# Schematic.net
KiCad netlist of a schematic drawn in EAGLE
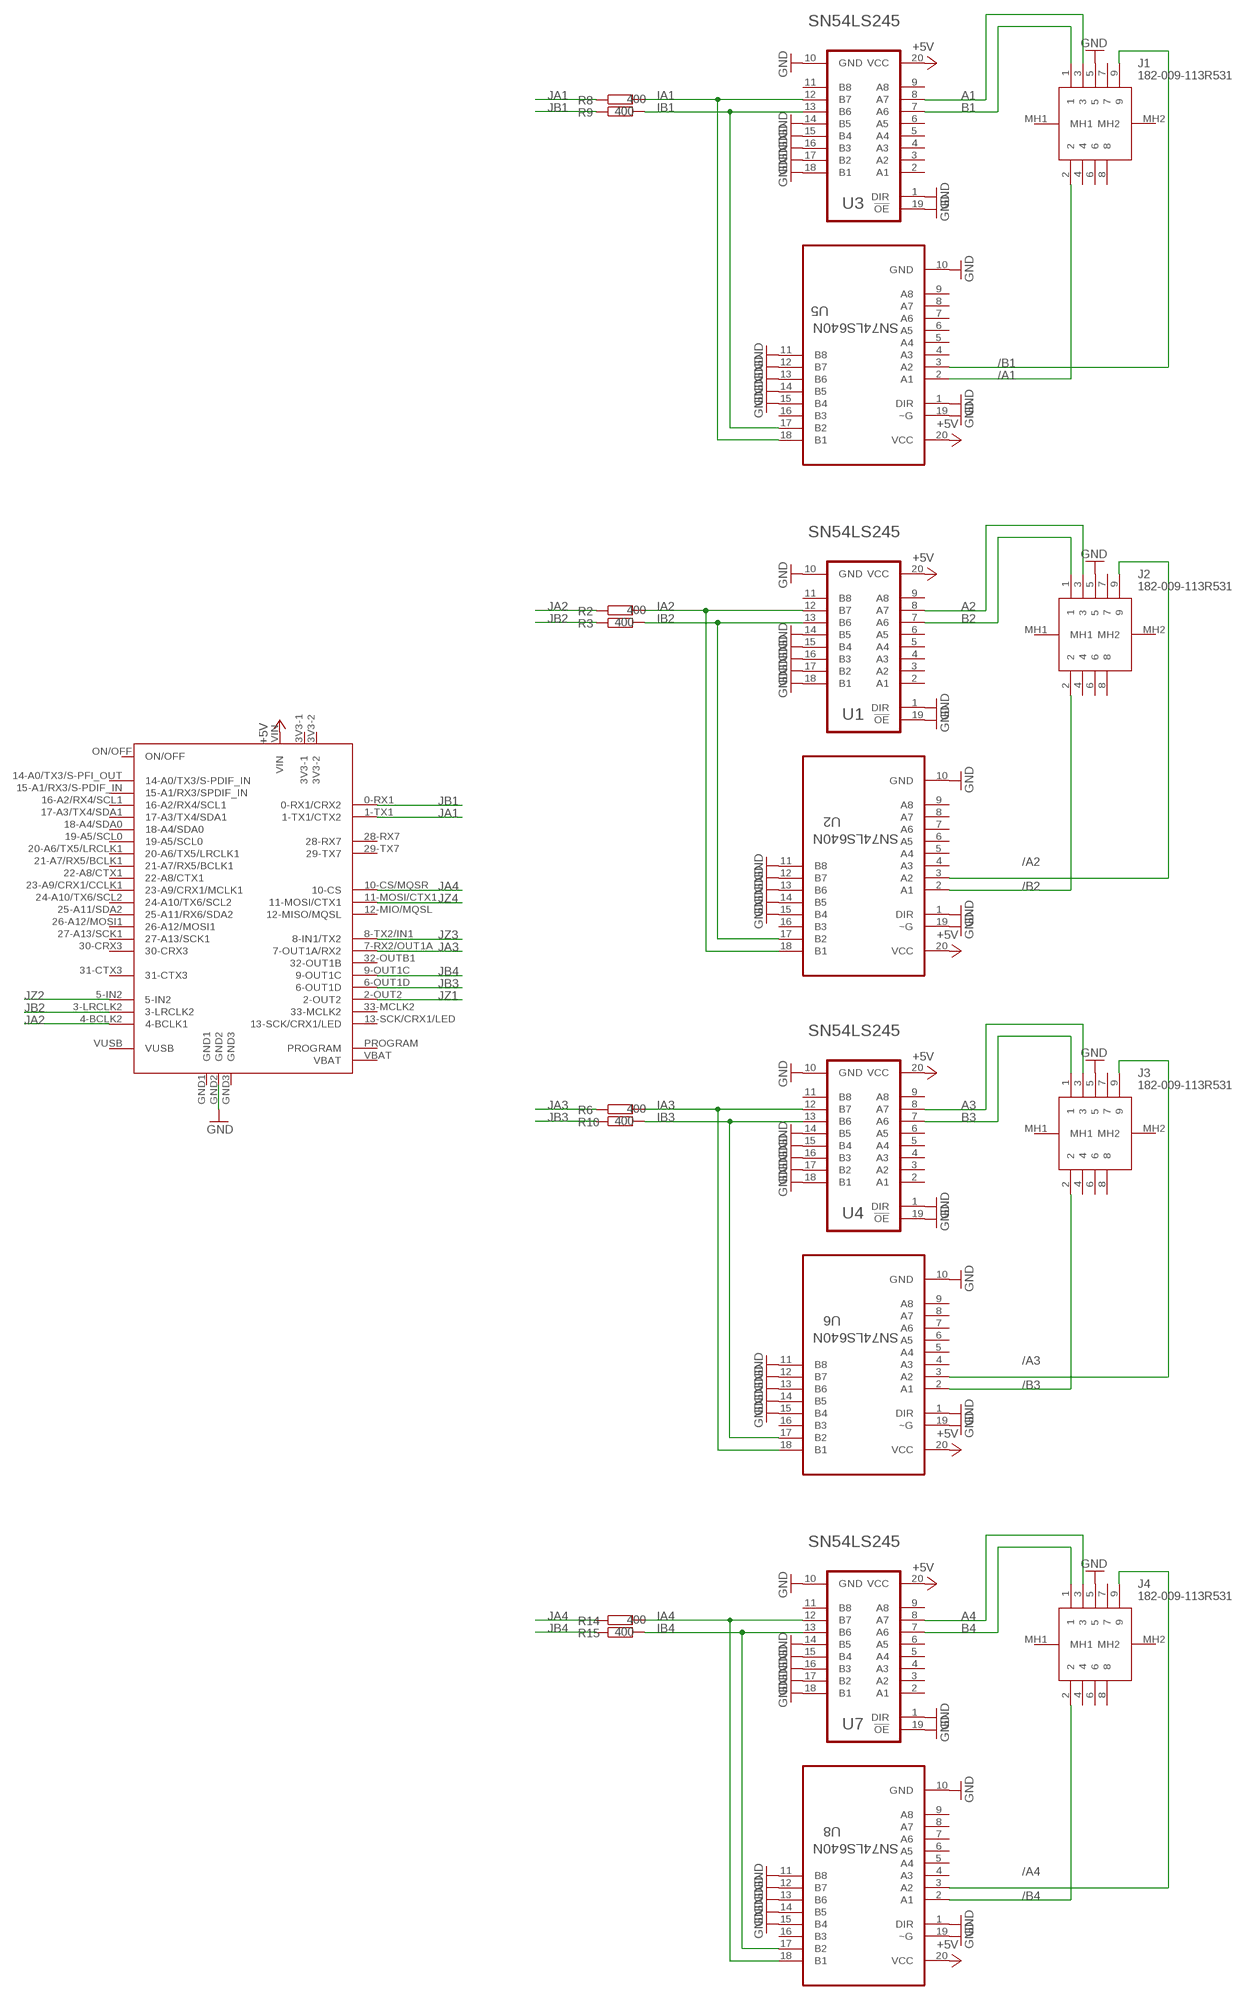
[diagram p0: schematic, sheet 1]

(export (version "E")
  (design (tool "Eeschema 10.0.6"))
  (components
    (comp (ref "J1")
      (value "182-009-113R531")
      (footprint "eagle-import:182009113R531")
      (fields (field (name "MOUSER_PART_NUMBER") "636-182-009-113R531"))
      (libsource (lib "eagle-import") (part "182-009-113R531"))
    )
    (comp (ref "J2")
      (value "182-009-113R531")
      (footprint "eagle-import:182009113R531")
      (fields (field (name "MOUSER_PART_NUMBER") "636-182-009-113R531"))
      (libsource (lib "eagle-import") (part "182-009-113R531"))
    )
    (comp (ref "J3")
      (value "182-009-113R531")
      (footprint "eagle-import:182009113R531")
      (fields (field (name "MOUSER_PART_NUMBER") "636-182-009-113R531"))
      (libsource (lib "eagle-import") (part "182-009-113R531"))
    )
    (comp (ref "J4")
      (value "182-009-113R531")
      (footprint "eagle-import:182009113R531")
      (fields (field (name "MOUSER_PART_NUMBER") "636-182-009-113R531"))
      (libsource (lib "eagle-import") (part "182-009-113R531"))
    )
    (comp (ref "R2")
      (value "400")
      (footprint "eagle-import:0204_7")
      (libsource (lib "eagle-import") (part "R-EU_0204/7"))
    )
    (comp (ref "R3")
      (value "400")
      (footprint "eagle-import:0204_7")
      (libsource (lib "eagle-import") (part "R-EU_0204/7"))
    )
    (comp (ref "R6")
      (value "400")
      (footprint "eagle-import:0204_7")
      (libsource (lib "eagle-import") (part "R-EU_0204/7"))
    )
    (comp (ref "R8")
      (value "400")
      (footprint "eagle-import:0204_7")
      (libsource (lib "eagle-import") (part "R-EU_0204/7"))
    )
    (comp (ref "R9")
      (value "400")
      (footprint "eagle-import:0204_7")
      (libsource (lib "eagle-import") (part "R-EU_0204/7"))
    )
    (comp (ref "R10")
      (value "400")
      (footprint "eagle-import:0204_7")
      (libsource (lib "eagle-import") (part "R-EU_0204/7"))
    )
    (comp (ref "R14")
      (value "400")
      (footprint "eagle-import:0204_7")
      (libsource (lib "eagle-import") (part "R-EU_0204/7"))
    )
    (comp (ref "R15")
      (value "400")
      (footprint "eagle-import:0204_7")
      (libsource (lib "eagle-import") (part "R-EU_0204/7"))
    )
    (comp (ref "U$1")
      (value "TEENSY40")
      (footprint "eagle-import:TEENSY40")
      (libsource (lib "eagle-import") (part "TEENSY40"))
    )
    (comp (ref "U1")
      (value "TEXAS_INSTRUMENTS_SN54LS245TEXAS_INSTRUMENTS_SN54LS245_0_0")
      (footprint "eagle-import:TEXAS_INSTRUMENTS_SN54LS245_0")
      (fields (field (name "MF") "Texas Instruments") (field (name "MPN") "SN54LS245"))
      (libsource (lib "eagle-import") (part "TEXAS_INSTRUMENTS_SN54LS245TEXAS_INSTRUMENTS_SN54LS245_0_0"))
    )
    (comp (ref "U2")
      (value "SN74LS640N")
      (footprint "eagle-import:DIP254P762X508-20")
      (fields (field (name "MF") "Texas Instruments"))
      (libsource (lib "eagle-import") (part "SN74LS640N"))
    )
    (comp (ref "U3")
      (value "TEXAS_INSTRUMENTS_SN54LS245TEXAS_INSTRUMENTS_SN54LS245_0_0")
      (footprint "eagle-import:TEXAS_INSTRUMENTS_SN54LS245_0")
      (fields (field (name "MF") "Texas Instruments") (field (name "MPN") "SN54LS245"))
      (libsource (lib "eagle-import") (part "TEXAS_INSTRUMENTS_SN54LS245TEXAS_INSTRUMENTS_SN54LS245_0_0"))
    )
    (comp (ref "U4")
      (value "TEXAS_INSTRUMENTS_SN54LS245TEXAS_INSTRUMENTS_SN54LS245_0_0")
      (footprint "eagle-import:TEXAS_INSTRUMENTS_SN54LS245_0")
      (fields (field (name "MF") "Texas Instruments") (field (name "MPN") "SN54LS245"))
      (libsource (lib "eagle-import") (part "TEXAS_INSTRUMENTS_SN54LS245TEXAS_INSTRUMENTS_SN54LS245_0_0"))
    )
    (comp (ref "U5")
      (value "SN74LS640N")
      (footprint "eagle-import:DIP254P762X508-20")
      (fields (field (name "MF") "Texas Instruments"))
      (libsource (lib "eagle-import") (part "SN74LS640N"))
    )
    (comp (ref "U6")
      (value "SN74LS640N")
      (footprint "eagle-import:DIP254P762X508-20")
      (fields (field (name "MF") "Texas Instruments"))
      (libsource (lib "eagle-import") (part "SN74LS640N"))
    )
    (comp (ref "U7")
      (value "TEXAS_INSTRUMENTS_SN54LS245TEXAS_INSTRUMENTS_SN54LS245_0_0")
      (footprint "eagle-import:TEXAS_INSTRUMENTS_SN54LS245_0")
      (fields (field (name "MF") "Texas Instruments") (field (name "MPN") "SN54LS245"))
      (libsource (lib "eagle-import") (part "TEXAS_INSTRUMENTS_SN54LS245TEXAS_INSTRUMENTS_SN54LS245_0_0"))
    )
    (comp (ref "U8")
      (value "SN74LS640N")
      (footprint "eagle-import:DIP254P762X508-20")
      (fields (field (name "MF") "Texas Instruments"))
      (libsource (lib "eagle-import") (part "SN74LS640N"))
    )
  )
  (nets
    (net (code "1") (name "+5V") (class "Default")
      (node (ref "U$1") (pin "VIN") (pinfunction "VIN_VIN") (pintype "bidirectional"))
      (node (ref "U1") (pin "20") (pinfunction "VCC_20") (pintype "power_in"))
      (node (ref "U2") (pin "20") (pinfunction "VCC_20") (pintype "power_in"))
      (node (ref "U3") (pin "20") (pinfunction "VCC_20") (pintype "power_in"))
      (node (ref "U4") (pin "20") (pinfunction "VCC_20") (pintype "power_in"))
      (node (ref "U5") (pin "20") (pinfunction "VCC_20") (pintype "power_in"))
      (node (ref "U6") (pin "20") (pinfunction "VCC_20") (pintype "power_in"))
      (node (ref "U7") (pin "20") (pinfunction "VCC_20") (pintype "power_in"))
      (node (ref "U8") (pin "20") (pinfunction "VCC_20") (pintype "power_in"))
    )
    (net (code "2") (name "/A1") (class "Default")
      (node (ref "J1") (pin "3") (pinfunction "3_3") (pintype "bidirectional"))
      (node (ref "U3") (pin "8") (pinfunction "A7_8") (pintype "bidirectional"))
    )
    (net (code "3") (name "/A2") (class "Default")
      (node (ref "J2") (pin "3") (pinfunction "3_3") (pintype "bidirectional"))
      (node (ref "U1") (pin "8") (pinfunction "A7_8") (pintype "bidirectional"))
    )
    (net (code "4") (name "/A3") (class "Default")
      (node (ref "J3") (pin "3") (pinfunction "3_3") (pintype "bidirectional"))
      (node (ref "U4") (pin "8") (pinfunction "A7_8") (pintype "bidirectional"))
    )
    (net (code "5") (name "/A4") (class "Default")
      (node (ref "J4") (pin "3") (pinfunction "3_3") (pintype "bidirectional"))
      (node (ref "U7") (pin "8") (pinfunction "A7_8") (pintype "bidirectional"))
    )
    (net (code "6") (name "/B1") (class "Default")
      (node (ref "J1") (pin "1") (pinfunction "1_1") (pintype "bidirectional"))
      (node (ref "U3") (pin "7") (pinfunction "A6_7") (pintype "bidirectional"))
    )
    (net (code "7") (name "/B2") (class "Default")
      (node (ref "J2") (pin "1") (pinfunction "1_1") (pintype "bidirectional"))
      (node (ref "U1") (pin "7") (pinfunction "A6_7") (pintype "bidirectional"))
    )
    (net (code "8") (name "/B3") (class "Default")
      (node (ref "J3") (pin "1") (pinfunction "1_1") (pintype "bidirectional"))
      (node (ref "U4") (pin "7") (pinfunction "A6_7") (pintype "bidirectional"))
    )
    (net (code "9") (name "/B4") (class "Default")
      (node (ref "J4") (pin "1") (pinfunction "1_1") (pintype "bidirectional"))
      (node (ref "U7") (pin "7") (pinfunction "A6_7") (pintype "bidirectional"))
    )
    (net (code "10") (name "/IA1") (class "Default")
      (node (ref "R8") (pin "2") (pinfunction "2_2") (pintype "passive"))
      (node (ref "U3") (pin "12") (pinfunction "B7_12") (pintype "bidirectional"))
      (node (ref "U5") (pin "18") (pinfunction "B1_18") (pintype "bidirectional"))
    )
    (net (code "11") (name "/IA2") (class "Default")
      (node (ref "R2") (pin "2") (pinfunction "2_2") (pintype "passive"))
      (node (ref "U1") (pin "12") (pinfunction "B7_12") (pintype "bidirectional"))
      (node (ref "U2") (pin "18") (pinfunction "B1_18") (pintype "bidirectional"))
    )
    (net (code "12") (name "/IA3") (class "Default")
      (node (ref "R6") (pin "2") (pinfunction "2_2") (pintype "passive"))
      (node (ref "U4") (pin "12") (pinfunction "B7_12") (pintype "bidirectional"))
      (node (ref "U6") (pin "18") (pinfunction "B1_18") (pintype "bidirectional"))
    )
    (net (code "13") (name "/IA4") (class "Default")
      (node (ref "R14") (pin "2") (pinfunction "2_2") (pintype "passive"))
      (node (ref "U7") (pin "12") (pinfunction "B7_12") (pintype "bidirectional"))
      (node (ref "U8") (pin "18") (pinfunction "B1_18") (pintype "bidirectional"))
    )
    (net (code "14") (name "/IB1") (class "Default")
      (node (ref "R9") (pin "2") (pinfunction "2_2") (pintype "passive"))
      (node (ref "U3") (pin "13") (pinfunction "B6_13") (pintype "bidirectional"))
      (node (ref "U5") (pin "17") (pinfunction "B2_17") (pintype "bidirectional"))
    )
    (net (code "15") (name "/IB2") (class "Default")
      (node (ref "R3") (pin "2") (pinfunction "2_2") (pintype "passive"))
      (node (ref "U1") (pin "13") (pinfunction "B6_13") (pintype "bidirectional"))
      (node (ref "U2") (pin "17") (pinfunction "B2_17") (pintype "bidirectional"))
    )
    (net (code "16") (name "/IB3") (class "Default")
      (node (ref "R10") (pin "2") (pinfunction "2_2") (pintype "passive"))
      (node (ref "U4") (pin "13") (pinfunction "B6_13") (pintype "bidirectional"))
      (node (ref "U6") (pin "17") (pinfunction "B2_17") (pintype "bidirectional"))
    )
    (net (code "17") (name "/IB4") (class "Default")
      (node (ref "R15") (pin "2") (pinfunction "2_2") (pintype "passive"))
      (node (ref "U7") (pin "13") (pinfunction "B6_13") (pintype "bidirectional"))
      (node (ref "U8") (pin "17") (pinfunction "B2_17") (pintype "bidirectional"))
    )
    (net (code "18") (name "/JA1") (class "Default")
      (node (ref "R8") (pin "1") (pinfunction "1_1") (pintype "passive"))
      (node (ref "U$1") (pin "1-TX1") (pinfunction "1-TX1/CTX2_1-TX1") (pintype "bidirectional"))
    )
    (net (code "19") (name "/JA2") (class "Default")
      (node (ref "R2") (pin "1") (pinfunction "1_1") (pintype "passive"))
      (node (ref "U$1") (pin "4-BCLK2") (pinfunction "4-BCLK1_4-BCLK2") (pintype "bidirectional"))
    )
    (net (code "20") (name "/JA3") (class "Default")
      (node (ref "R6") (pin "1") (pinfunction "1_1") (pintype "passive"))
      (node (ref "U$1") (pin "7-RX2/OUT1A") (pinfunction "7-OUT1A/RX2_7-RX2/OUT1A") (pintype "bidirectional"))
    )
    (net (code "21") (name "/JA4") (class "Default")
      (node (ref "R14") (pin "1") (pinfunction "1_1") (pintype "passive"))
      (node (ref "U$1") (pin "10-CS/MQSR") (pinfunction "10-CS_10-CS/MQSR") (pintype "bidirectional"))
    )
    (net (code "22") (name "/JB1") (class "Default")
      (node (ref "R9") (pin "1") (pinfunction "1_1") (pintype "passive"))
      (node (ref "U$1") (pin "0-RX1") (pinfunction "0-RX1/CRX2_0-RX1") (pintype "bidirectional"))
    )
    (net (code "23") (name "/JB2") (class "Default")
      (node (ref "R3") (pin "1") (pinfunction "1_1") (pintype "passive"))
      (node (ref "U$1") (pin "3-LRCLK2") (pinfunction "3-LRCLK2_3-LRCLK2") (pintype "bidirectional"))
    )
    (net (code "24") (name "/JB3") (class "Default")
      (node (ref "R10") (pin "1") (pinfunction "1_1") (pintype "passive"))
      (node (ref "U$1") (pin "6-OUT1D") (pinfunction "6-OUT1D_6-OUT1D") (pintype "bidirectional"))
    )
    (net (code "25") (name "/JB4") (class "Default")
      (node (ref "R15") (pin "1") (pinfunction "1_1") (pintype "passive"))
      (node (ref "U$1") (pin "9-OUT1C") (pinfunction "9-OUT1C_9-OUT1C") (pintype "bidirectional"))
    )
    (net (code "26") (name "/JZ1") (class "Default")
      (node (ref "U$1") (pin "2-OUT2") (pinfunction "2-OUT2_2-OUT2") (pintype "bidirectional"))
    )
    (net (code "27") (name "/JZ2") (class "Default")
      (node (ref "U$1") (pin "5-IN2") (pinfunction "5-IN2_5-IN2") (pintype "bidirectional"))
    )
    (net (code "28") (name "/JZ3") (class "Default")
      (node (ref "U$1") (pin "8-TX2/IN1") (pinfunction "8-IN1/TX2_8-TX2/IN1") (pintype "bidirectional"))
    )
    (net (code "29") (name "/JZ4") (class "Default")
      (node (ref "U$1") (pin "11-MOSI/CTX1") (pinfunction "11-MOSI/CTX1_11-MOSI/CTX1") (pintype "bidirectional"))
    )
    (net (code "30") (name "/{slash}A1") (class "Default")
      (node (ref "J1") (pin "2") (pinfunction "2_2") (pintype "bidirectional"))
      (node (ref "U5") (pin "2") (pinfunction "A1_2") (pintype "bidirectional"))
    )
    (net (code "31") (name "/{slash}A2") (class "Default")
      (node (ref "J2") (pin "2") (pinfunction "2_2") (pintype "bidirectional"))
      (node (ref "U2") (pin "2") (pinfunction "A1_2") (pintype "bidirectional"))
    )
    (net (code "32") (name "/{slash}A3") (class "Default")
      (node (ref "J3") (pin "2") (pinfunction "2_2") (pintype "bidirectional"))
      (node (ref "U6") (pin "2") (pinfunction "A1_2") (pintype "bidirectional"))
    )
    (net (code "33") (name "/{slash}A4") (class "Default")
      (node (ref "J4") (pin "2") (pinfunction "2_2") (pintype "bidirectional"))
      (node (ref "U8") (pin "2") (pinfunction "A1_2") (pintype "bidirectional"))
    )
    (net (code "34") (name "/{slash}B1") (class "Default")
      (node (ref "J1") (pin "9") (pinfunction "9_9") (pintype "bidirectional"))
      (node (ref "U5") (pin "3") (pinfunction "A2_3") (pintype "bidirectional"))
    )
    (net (code "35") (name "/{slash}B2") (class "Default")
      (node (ref "J2") (pin "9") (pinfunction "9_9") (pintype "bidirectional"))
      (node (ref "U2") (pin "3") (pinfunction "A2_3") (pintype "bidirectional"))
    )
    (net (code "36") (name "/{slash}B3") (class "Default")
      (node (ref "J3") (pin "9") (pinfunction "9_9") (pintype "bidirectional"))
      (node (ref "U6") (pin "3") (pinfunction "A2_3") (pintype "bidirectional"))
    )
    (net (code "37") (name "/{slash}B4") (class "Default")
      (node (ref "J4") (pin "9") (pinfunction "9_9") (pintype "bidirectional"))
      (node (ref "U8") (pin "3") (pinfunction "A2_3") (pintype "bidirectional"))
    )
    (net (code "38") (name "GND") (class "Default")
      (node (ref "J1") (pin "5") (pinfunction "5_5") (pintype "bidirectional"))
      (node (ref "J2") (pin "5") (pinfunction "5_5") (pintype "bidirectional"))
      (node (ref "J3") (pin "5") (pinfunction "5_5") (pintype "bidirectional"))
      (node (ref "J4") (pin "5") (pinfunction "5_5") (pintype "bidirectional"))
      (node (ref "U$1") (pin "GND2") (pinfunction "GND2_GND2") (pintype "bidirectional"))
      (node (ref "U1") (pin "1") (pinfunction "DIR_1") (pintype "input"))
      (node (ref "U1") (pin "10") (pinfunction "GND_10") (pintype "power_in"))
      (node (ref "U1") (pin "14") (pinfunction "B5_14") (pintype "bidirectional"))
      (node (ref "U1") (pin "15") (pinfunction "B4_15") (pintype "bidirectional"))
      (node (ref "U1") (pin "16") (pinfunction "B3_16") (pintype "bidirectional"))
      (node (ref "U1") (pin "17") (pinfunction "B2_17") (pintype "bidirectional"))
      (node (ref "U1") (pin "18") (pinfunction "B1_18") (pintype "bidirectional"))
      (node (ref "U1") (pin "19") (pinfunction "~{OE}_19") (pintype "input"))
      (node (ref "U2") (pin "1") (pinfunction "DIR_1") (pintype "input"))
      (node (ref "U2") (pin "10") (pinfunction "GND_10") (pintype "passive"))
      (node (ref "U2") (pin "11") (pinfunction "B8_11") (pintype "bidirectional"))
      (node (ref "U2") (pin "12") (pinfunction "B7_12") (pintype "bidirectional"))
      (node (ref "U2") (pin "13") (pinfunction "B6_13") (pintype "bidirectional"))
      (node (ref "U2") (pin "14") (pinfunction "B5_14") (pintype "bidirectional"))
      (node (ref "U2") (pin "15") (pinfunction "B4_15") (pintype "bidirectional"))
      (node (ref "U2") (pin "19") (pinfunction "~{G}_19") (pintype "input"))
      (node (ref "U3") (pin "1") (pinfunction "DIR_1") (pintype "input"))
      (node (ref "U3") (pin "10") (pinfunction "GND_10") (pintype "power_in"))
      (node (ref "U3") (pin "14") (pinfunction "B5_14") (pintype "bidirectional"))
      (node (ref "U3") (pin "15") (pinfunction "B4_15") (pintype "bidirectional"))
      (node (ref "U3") (pin "16") (pinfunction "B3_16") (pintype "bidirectional"))
      (node (ref "U3") (pin "17") (pinfunction "B2_17") (pintype "bidirectional"))
      (node (ref "U3") (pin "18") (pinfunction "B1_18") (pintype "bidirectional"))
      (node (ref "U3") (pin "19") (pinfunction "~{OE}_19") (pintype "input"))
      (node (ref "U4") (pin "1") (pinfunction "DIR_1") (pintype "input"))
      (node (ref "U4") (pin "10") (pinfunction "GND_10") (pintype "power_in"))
      (node (ref "U4") (pin "14") (pinfunction "B5_14") (pintype "bidirectional"))
      (node (ref "U4") (pin "15") (pinfunction "B4_15") (pintype "bidirectional"))
      (node (ref "U4") (pin "16") (pinfunction "B3_16") (pintype "bidirectional"))
      (node (ref "U4") (pin "17") (pinfunction "B2_17") (pintype "bidirectional"))
      (node (ref "U4") (pin "18") (pinfunction "B1_18") (pintype "bidirectional"))
      (node (ref "U4") (pin "19") (pinfunction "~{OE}_19") (pintype "input"))
      (node (ref "U5") (pin "1") (pinfunction "DIR_1") (pintype "input"))
      (node (ref "U5") (pin "10") (pinfunction "GND_10") (pintype "passive"))
      (node (ref "U5") (pin "11") (pinfunction "B8_11") (pintype "bidirectional"))
      (node (ref "U5") (pin "12") (pinfunction "B7_12") (pintype "bidirectional"))
      (node (ref "U5") (pin "13") (pinfunction "B6_13") (pintype "bidirectional"))
      (node (ref "U5") (pin "14") (pinfunction "B5_14") (pintype "bidirectional"))
      (node (ref "U5") (pin "15") (pinfunction "B4_15") (pintype "bidirectional"))
      (node (ref "U5") (pin "19") (pinfunction "~{G}_19") (pintype "input"))
      (node (ref "U6") (pin "1") (pinfunction "DIR_1") (pintype "input"))
      (node (ref "U6") (pin "10") (pinfunction "GND_10") (pintype "passive"))
      (node (ref "U6") (pin "11") (pinfunction "B8_11") (pintype "bidirectional"))
      (node (ref "U6") (pin "12") (pinfunction "B7_12") (pintype "bidirectional"))
      (node (ref "U6") (pin "13") (pinfunction "B6_13") (pintype "bidirectional"))
      (node (ref "U6") (pin "14") (pinfunction "B5_14") (pintype "bidirectional"))
      (node (ref "U6") (pin "15") (pinfunction "B4_15") (pintype "bidirectional"))
      (node (ref "U6") (pin "19") (pinfunction "~{G}_19") (pintype "input"))
      (node (ref "U7") (pin "1") (pinfunction "DIR_1") (pintype "input"))
      (node (ref "U7") (pin "10") (pinfunction "GND_10") (pintype "power_in"))
      (node (ref "U7") (pin "14") (pinfunction "B5_14") (pintype "bidirectional"))
      (node (ref "U7") (pin "15") (pinfunction "B4_15") (pintype "bidirectional"))
      (node (ref "U7") (pin "16") (pinfunction "B3_16") (pintype "bidirectional"))
      (node (ref "U7") (pin "17") (pinfunction "B2_17") (pintype "bidirectional"))
      (node (ref "U7") (pin "18") (pinfunction "B1_18") (pintype "bidirectional"))
      (node (ref "U7") (pin "19") (pinfunction "~{OE}_19") (pintype "input"))
      (node (ref "U8") (pin "1") (pinfunction "DIR_1") (pintype "input"))
      (node (ref "U8") (pin "10") (pinfunction "GND_10") (pintype "passive"))
      (node (ref "U8") (pin "11") (pinfunction "B8_11") (pintype "bidirectional"))
      (node (ref "U8") (pin "12") (pinfunction "B7_12") (pintype "bidirectional"))
      (node (ref "U8") (pin "13") (pinfunction "B6_13") (pintype "bidirectional"))
      (node (ref "U8") (pin "14") (pinfunction "B5_14") (pintype "bidirectional"))
      (node (ref "U8") (pin "15") (pinfunction "B4_15") (pintype "bidirectional"))
      (node (ref "U8") (pin "19") (pinfunction "~{G}_19") (pintype "input"))
    )
    (net (code "39") (name "unconnected-(J1-Pad4)") (class "Default")
      (node (ref "J1") (pin "4") (pinfunction "4_4") (pintype "bidirectional"))
    )
    (net (code "40") (name "unconnected-(J1-Pad6)") (class "Default")
      (node (ref "J1") (pin "6") (pinfunction "6_6") (pintype "bidirectional"))
    )
    (net (code "41") (name "unconnected-(J1-Pad7)") (class "Default")
      (node (ref "J1") (pin "7") (pinfunction "7_7") (pintype "bidirectional"))
    )
    (net (code "42") (name "unconnected-(J1-Pad8)") (class "Default")
      (node (ref "J1") (pin "8") (pinfunction "8_8") (pintype "bidirectional"))
    )
    (net (code "43") (name "unconnected-(J1-PadMH1)") (class "Default")
      (node (ref "J1") (pin "MH1") (pinfunction "MH1_MH1") (pintype "bidirectional"))
    )
    (net (code "44") (name "unconnected-(J1-PadMH2)") (class "Default")
      (node (ref "J1") (pin "MH2") (pinfunction "MH2_MH2") (pintype "bidirectional"))
    )
    (net (code "45") (name "unconnected-(J2-Pad4)") (class "Default")
      (node (ref "J2") (pin "4") (pinfunction "4_4") (pintype "bidirectional"))
    )
    (net (code "46") (name "unconnected-(J2-Pad6)") (class "Default")
      (node (ref "J2") (pin "6") (pinfunction "6_6") (pintype "bidirectional"))
    )
    (net (code "47") (name "unconnected-(J2-Pad7)") (class "Default")
      (node (ref "J2") (pin "7") (pinfunction "7_7") (pintype "bidirectional"))
    )
    (net (code "48") (name "unconnected-(J2-Pad8)") (class "Default")
      (node (ref "J2") (pin "8") (pinfunction "8_8") (pintype "bidirectional"))
    )
    (net (code "49") (name "unconnected-(J2-PadMH1)") (class "Default")
      (node (ref "J2") (pin "MH1") (pinfunction "MH1_MH1") (pintype "bidirectional"))
    )
    (net (code "50") (name "unconnected-(J2-PadMH2)") (class "Default")
      (node (ref "J2") (pin "MH2") (pinfunction "MH2_MH2") (pintype "bidirectional"))
    )
    (net (code "51") (name "unconnected-(J3-Pad4)") (class "Default")
      (node (ref "J3") (pin "4") (pinfunction "4_4") (pintype "bidirectional"))
    )
    (net (code "52") (name "unconnected-(J3-Pad6)") (class "Default")
      (node (ref "J3") (pin "6") (pinfunction "6_6") (pintype "bidirectional"))
    )
    (net (code "53") (name "unconnected-(J3-Pad7)") (class "Default")
      (node (ref "J3") (pin "7") (pinfunction "7_7") (pintype "bidirectional"))
    )
    (net (code "54") (name "unconnected-(J3-Pad8)") (class "Default")
      (node (ref "J3") (pin "8") (pinfunction "8_8") (pintype "bidirectional"))
    )
    (net (code "55") (name "unconnected-(J3-PadMH1)") (class "Default")
      (node (ref "J3") (pin "MH1") (pinfunction "MH1_MH1") (pintype "bidirectional"))
    )
    (net (code "56") (name "unconnected-(J3-PadMH2)") (class "Default")
      (node (ref "J3") (pin "MH2") (pinfunction "MH2_MH2") (pintype "bidirectional"))
    )
    (net (code "57") (name "unconnected-(J4-Pad4)") (class "Default")
      (node (ref "J4") (pin "4") (pinfunction "4_4") (pintype "bidirectional"))
    )
    (net (code "58") (name "unconnected-(J4-Pad6)") (class "Default")
      (node (ref "J4") (pin "6") (pinfunction "6_6") (pintype "bidirectional"))
    )
    (net (code "59") (name "unconnected-(J4-Pad7)") (class "Default")
      (node (ref "J4") (pin "7") (pinfunction "7_7") (pintype "bidirectional"))
    )
    (net (code "60") (name "unconnected-(J4-Pad8)") (class "Default")
      (node (ref "J4") (pin "8") (pinfunction "8_8") (pintype "bidirectional"))
    )
    (net (code "61") (name "unconnected-(J4-PadMH1)") (class "Default")
      (node (ref "J4") (pin "MH1") (pinfunction "MH1_MH1") (pintype "bidirectional"))
    )
    (net (code "62") (name "unconnected-(J4-PadMH2)") (class "Default")
      (node (ref "J4") (pin "MH2") (pinfunction "MH2_MH2") (pintype "bidirectional"))
    )
    (net (code "63") (name "unconnected-(U$1-12-MISO{slash}MQSL-Pad12-MIO{slash}MQSL)") (class "Default")
      (node (ref "U$1") (pin "12-MIO/MQSL") (pinfunction "12-MISO/MQSL_12-MIO/MQSL") (pintype "bidirectional"))
    )
    (net (code "64") (name "unconnected-(U$1-14-A0{slash}TX3{slash}S-PDIF_IN-Pad14-A0{slash}TX3{slash}S-PFI_OUT)") (class "Default")
      (node (ref "U$1") (pin "14-A0/TX3/S-PFI_OUT") (pinfunction "14-A0/TX3/S-PDIF_IN_14-A0/TX3/S-PFI_OUT") (pintype "bidirectional"))
    )
    (net (code "65") (name "unconnected-(U$1-15-A1{slash}RX3{slash}SPDIF_IN-Pad15-A1{slash}RX3{slash}S-PDIF_IN)") (class "Default")
      (node (ref "U$1") (pin "15-A1/RX3/S-PDIF_IN") (pinfunction "15-A1/RX3/SPDIF_IN_15-A1/RX3/S-PDIF_IN") (pintype "bidirectional"))
    )
    (net (code "66") (name "unconnected-(U$1-23-A9{slash}CRX1{slash}MCLK1-Pad23-A9{slash}CRX1{slash}CCLK1)") (class "Default")
      (node (ref "U$1") (pin "23-A9/CRX1/CCLK1") (pinfunction "23-A9/CRX1/MCLK1_23-A9/CRX1/CCLK1") (pintype "bidirectional"))
    )
    (net (code "67") (name "unconnected-(U$1-25-A11{slash}RX6{slash}SDA2-Pad25-A11{slash}SDA2)") (class "Default")
      (node (ref "U$1") (pin "25-A11/SDA2") (pinfunction "25-A11/RX6/SDA2_25-A11/SDA2") (pintype "bidirectional"))
    )
    (net (code "68") (name "unconnected-(U$1-32-OUT1B-Pad32-OUTB1)") (class "Default")
      (node (ref "U$1") (pin "32-OUTB1") (pinfunction "32-OUT1B_32-OUTB1") (pintype "bidirectional"))
    )
    (net (code "69") (name "unconnected-(U$1-Pad3V3-1)") (class "Default")
      (node (ref "U$1") (pin "3V3-1") (pinfunction "3V3-1_3V3-1") (pintype "bidirectional"))
    )
    (net (code "70") (name "unconnected-(U$1-Pad3V3-2)") (class "Default")
      (node (ref "U$1") (pin "3V3-2") (pinfunction "3V3-2_3V3-2") (pintype "bidirectional"))
    )
    (net (code "71") (name "unconnected-(U$1-Pad13-SCK{slash}CRX1{slash}LED)") (class "Default")
      (node (ref "U$1") (pin "13-SCK/CRX1/LED") (pinfunction "13-SCK/CRX1/LED_13-SCK/CRX1/LED") (pintype "bidirectional"))
    )
    (net (code "72") (name "unconnected-(U$1-Pad16-A2{slash}RX4{slash}SCL1)") (class "Default")
      (node (ref "U$1") (pin "16-A2/RX4/SCL1") (pinfunction "16-A2/RX4/SCL1_16-A2/RX4/SCL1") (pintype "bidirectional"))
    )
    (net (code "73") (name "unconnected-(U$1-Pad17-A3{slash}TX4{slash}SDA1)") (class "Default")
      (node (ref "U$1") (pin "17-A3/TX4/SDA1") (pinfunction "17-A3/TX4/SDA1_17-A3/TX4/SDA1") (pintype "bidirectional"))
    )
    (net (code "74") (name "unconnected-(U$1-Pad18-A4{slash}SDA0)") (class "Default")
      (node (ref "U$1") (pin "18-A4/SDA0") (pinfunction "18-A4/SDA0_18-A4/SDA0") (pintype "bidirectional"))
    )
    (net (code "75") (name "unconnected-(U$1-Pad19-A5{slash}SCL0)") (class "Default")
      (node (ref "U$1") (pin "19-A5/SCL0") (pinfunction "19-A5/SCL0_19-A5/SCL0") (pintype "bidirectional"))
    )
    (net (code "76") (name "unconnected-(U$1-Pad20-A6{slash}TX5{slash}LRCLK1)") (class "Default")
      (node (ref "U$1") (pin "20-A6/TX5/LRCLK1") (pinfunction "20-A6/TX5/LRCLK1_20-A6/TX5/LRCLK1") (pintype "bidirectional"))
    )
    (net (code "77") (name "unconnected-(U$1-Pad21-A7{slash}RX5{slash}BCLK1)") (class "Default")
      (node (ref "U$1") (pin "21-A7/RX5/BCLK1") (pinfunction "21-A7/RX5/BCLK1_21-A7/RX5/BCLK1") (pintype "bidirectional"))
    )
    (net (code "78") (name "unconnected-(U$1-Pad22-A8{slash}CTX1)") (class "Default")
      (node (ref "U$1") (pin "22-A8/CTX1") (pinfunction "22-A8/CTX1_22-A8/CTX1") (pintype "bidirectional"))
    )
    (net (code "79") (name "unconnected-(U$1-Pad24-A10{slash}TX6{slash}SCL2)") (class "Default")
      (node (ref "U$1") (pin "24-A10/TX6/SCL2") (pinfunction "24-A10/TX6/SCL2_24-A10/TX6/SCL2") (pintype "bidirectional"))
    )
    (net (code "80") (name "unconnected-(U$1-Pad26-A12{slash}MOSI1)") (class "Default")
      (node (ref "U$1") (pin "26-A12/MOSI1") (pinfunction "26-A12/MOSI1_26-A12/MOSI1") (pintype "bidirectional"))
    )
    (net (code "81") (name "unconnected-(U$1-Pad27-A13{slash}SCK1)") (class "Default")
      (node (ref "U$1") (pin "27-A13/SCK1") (pinfunction "27-A13/SCK1_27-A13/SCK1") (pintype "bidirectional"))
    )
    (net (code "82") (name "unconnected-(U$1-Pad28-RX7)") (class "Default")
      (node (ref "U$1") (pin "28-RX7") (pinfunction "28-RX7_28-RX7") (pintype "bidirectional"))
    )
    (net (code "83") (name "unconnected-(U$1-Pad29-TX7)") (class "Default")
      (node (ref "U$1") (pin "29-TX7") (pinfunction "29-TX7_29-TX7") (pintype "bidirectional"))
    )
    (net (code "84") (name "unconnected-(U$1-Pad30-CRX3)") (class "Default")
      (node (ref "U$1") (pin "30-CRX3") (pinfunction "30-CRX3_30-CRX3") (pintype "bidirectional"))
    )
    (net (code "85") (name "unconnected-(U$1-Pad31-CTX3)") (class "Default")
      (node (ref "U$1") (pin "31-CTX3") (pinfunction "31-CTX3_31-CTX3") (pintype "bidirectional"))
    )
    (net (code "86") (name "unconnected-(U$1-Pad33-MCLK2)") (class "Default")
      (node (ref "U$1") (pin "33-MCLK2") (pinfunction "33-MCLK2_33-MCLK2") (pintype "bidirectional"))
    )
    (net (code "87") (name "unconnected-(U$1-PadGND1)") (class "Default")
      (node (ref "U$1") (pin "GND1") (pinfunction "GND1_GND1") (pintype "bidirectional"))
    )
    (net (code "88") (name "unconnected-(U$1-PadGND3)") (class "Default")
      (node (ref "U$1") (pin "GND3") (pinfunction "GND3_GND3") (pintype "bidirectional"))
    )
    (net (code "89") (name "unconnected-(U$1-PadON{slash}OFF)") (class "Default")
      (node (ref "U$1") (pin "ON/OFF") (pinfunction "ON/OFF_ON/OFF") (pintype "bidirectional"))
    )
    (net (code "90") (name "unconnected-(U$1-PadPROGRAM)") (class "Default")
      (node (ref "U$1") (pin "PROGRAM") (pinfunction "PROGRAM_PROGRAM") (pintype "bidirectional"))
    )
    (net (code "91") (name "unconnected-(U$1-PadVBAT)") (class "Default")
      (node (ref "U$1") (pin "VBAT") (pinfunction "VBAT_VBAT") (pintype "bidirectional"))
    )
    (net (code "92") (name "unconnected-(U$1-PadVUSB)") (class "Default")
      (node (ref "U$1") (pin "VUSB") (pinfunction "VUSB_VUSB") (pintype "bidirectional"))
    )
    (net (code "93") (name "unconnected-(U1-A1-Pad2)") (class "Default")
      (node (ref "U1") (pin "2") (pinfunction "A1_2") (pintype "bidirectional"))
    )
    (net (code "94") (name "unconnected-(U1-A2-Pad3)") (class "Default")
      (node (ref "U1") (pin "3") (pinfunction "A2_3") (pintype "bidirectional"))
    )
    (net (code "95") (name "unconnected-(U1-A3-Pad4)") (class "Default")
      (node (ref "U1") (pin "4") (pinfunction "A3_4") (pintype "bidirectional"))
    )
    (net (code "96") (name "unconnected-(U1-A4-Pad5)") (class "Default")
      (node (ref "U1") (pin "5") (pinfunction "A4_5") (pintype "bidirectional"))
    )
    (net (code "97") (name "unconnected-(U1-A5-Pad6)") (class "Default")
      (node (ref "U1") (pin "6") (pinfunction "A5_6") (pintype "bidirectional"))
    )
    (net (code "98") (name "unconnected-(U1-A8-Pad9)") (class "Default")
      (node (ref "U1") (pin "9") (pinfunction "A8_9") (pintype "bidirectional"))
    )
    (net (code "99") (name "unconnected-(U1-B8-Pad11)") (class "Default")
      (node (ref "U1") (pin "11") (pinfunction "B8_11") (pintype "bidirectional"))
    )
    (net (code "100") (name "unconnected-(U2-A3-Pad4)") (class "Default")
      (node (ref "U2") (pin "4") (pinfunction "A3_4") (pintype "bidirectional"))
    )
    (net (code "101") (name "unconnected-(U2-A4-Pad5)") (class "Default")
      (node (ref "U2") (pin "5") (pinfunction "A4_5") (pintype "bidirectional"))
    )
    (net (code "102") (name "unconnected-(U2-A5-Pad6)") (class "Default")
      (node (ref "U2") (pin "6") (pinfunction "A5_6") (pintype "bidirectional"))
    )
    (net (code "103") (name "unconnected-(U2-A6-Pad7)") (class "Default")
      (node (ref "U2") (pin "7") (pinfunction "A6_7") (pintype "bidirectional"))
    )
    (net (code "104") (name "unconnected-(U2-A7-Pad8)") (class "Default")
      (node (ref "U2") (pin "8") (pinfunction "A7_8") (pintype "bidirectional"))
    )
    (net (code "105") (name "unconnected-(U2-A8-Pad9)") (class "Default")
      (node (ref "U2") (pin "9") (pinfunction "A8_9") (pintype "bidirectional"))
    )
    (net (code "106") (name "unconnected-(U2-B3-Pad16)") (class "Default")
      (node (ref "U2") (pin "16") (pinfunction "B3_16") (pintype "bidirectional"))
    )
    (net (code "107") (name "unconnected-(U3-A1-Pad2)") (class "Default")
      (node (ref "U3") (pin "2") (pinfunction "A1_2") (pintype "bidirectional"))
    )
    (net (code "108") (name "unconnected-(U3-A2-Pad3)") (class "Default")
      (node (ref "U3") (pin "3") (pinfunction "A2_3") (pintype "bidirectional"))
    )
    (net (code "109") (name "unconnected-(U3-A3-Pad4)") (class "Default")
      (node (ref "U3") (pin "4") (pinfunction "A3_4") (pintype "bidirectional"))
    )
    (net (code "110") (name "unconnected-(U3-A4-Pad5)") (class "Default")
      (node (ref "U3") (pin "5") (pinfunction "A4_5") (pintype "bidirectional"))
    )
    (net (code "111") (name "unconnected-(U3-A5-Pad6)") (class "Default")
      (node (ref "U3") (pin "6") (pinfunction "A5_6") (pintype "bidirectional"))
    )
    (net (code "112") (name "unconnected-(U3-A8-Pad9)") (class "Default")
      (node (ref "U3") (pin "9") (pinfunction "A8_9") (pintype "bidirectional"))
    )
    (net (code "113") (name "unconnected-(U3-B8-Pad11)") (class "Default")
      (node (ref "U3") (pin "11") (pinfunction "B8_11") (pintype "bidirectional"))
    )
    (net (code "114") (name "unconnected-(U4-A1-Pad2)") (class "Default")
      (node (ref "U4") (pin "2") (pinfunction "A1_2") (pintype "bidirectional"))
    )
    (net (code "115") (name "unconnected-(U4-A2-Pad3)") (class "Default")
      (node (ref "U4") (pin "3") (pinfunction "A2_3") (pintype "bidirectional"))
    )
    (net (code "116") (name "unconnected-(U4-A3-Pad4)") (class "Default")
      (node (ref "U4") (pin "4") (pinfunction "A3_4") (pintype "bidirectional"))
    )
    (net (code "117") (name "unconnected-(U4-A4-Pad5)") (class "Default")
      (node (ref "U4") (pin "5") (pinfunction "A4_5") (pintype "bidirectional"))
    )
    (net (code "118") (name "unconnected-(U4-A5-Pad6)") (class "Default")
      (node (ref "U4") (pin "6") (pinfunction "A5_6") (pintype "bidirectional"))
    )
    (net (code "119") (name "unconnected-(U4-A8-Pad9)") (class "Default")
      (node (ref "U4") (pin "9") (pinfunction "A8_9") (pintype "bidirectional"))
    )
    (net (code "120") (name "unconnected-(U4-B8-Pad11)") (class "Default")
      (node (ref "U4") (pin "11") (pinfunction "B8_11") (pintype "bidirectional"))
    )
    (net (code "121") (name "unconnected-(U5-A3-Pad4)") (class "Default")
      (node (ref "U5") (pin "4") (pinfunction "A3_4") (pintype "bidirectional"))
    )
    (net (code "122") (name "unconnected-(U5-A4-Pad5)") (class "Default")
      (node (ref "U5") (pin "5") (pinfunction "A4_5") (pintype "bidirectional"))
    )
    (net (code "123") (name "unconnected-(U5-A5-Pad6)") (class "Default")
      (node (ref "U5") (pin "6") (pinfunction "A5_6") (pintype "bidirectional"))
    )
    (net (code "124") (name "unconnected-(U5-A6-Pad7)") (class "Default")
      (node (ref "U5") (pin "7") (pinfunction "A6_7") (pintype "bidirectional"))
    )
    (net (code "125") (name "unconnected-(U5-A7-Pad8)") (class "Default")
      (node (ref "U5") (pin "8") (pinfunction "A7_8") (pintype "bidirectional"))
    )
    (net (code "126") (name "unconnected-(U5-A8-Pad9)") (class "Default")
      (node (ref "U5") (pin "9") (pinfunction "A8_9") (pintype "bidirectional"))
    )
    (net (code "127") (name "unconnected-(U5-B3-Pad16)") (class "Default")
      (node (ref "U5") (pin "16") (pinfunction "B3_16") (pintype "bidirectional"))
    )
    (net (code "128") (name "unconnected-(U6-A3-Pad4)") (class "Default")
      (node (ref "U6") (pin "4") (pinfunction "A3_4") (pintype "bidirectional"))
    )
    (net (code "129") (name "unconnected-(U6-A4-Pad5)") (class "Default")
      (node (ref "U6") (pin "5") (pinfunction "A4_5") (pintype "bidirectional"))
    )
    (net (code "130") (name "unconnected-(U6-A5-Pad6)") (class "Default")
      (node (ref "U6") (pin "6") (pinfunction "A5_6") (pintype "bidirectional"))
    )
    (net (code "131") (name "unconnected-(U6-A6-Pad7)") (class "Default")
      (node (ref "U6") (pin "7") (pinfunction "A6_7") (pintype "bidirectional"))
    )
    (net (code "132") (name "unconnected-(U6-A7-Pad8)") (class "Default")
      (node (ref "U6") (pin "8") (pinfunction "A7_8") (pintype "bidirectional"))
    )
    (net (code "133") (name "unconnected-(U6-A8-Pad9)") (class "Default")
      (node (ref "U6") (pin "9") (pinfunction "A8_9") (pintype "bidirectional"))
    )
    (net (code "134") (name "unconnected-(U6-B3-Pad16)") (class "Default")
      (node (ref "U6") (pin "16") (pinfunction "B3_16") (pintype "bidirectional"))
    )
    (net (code "135") (name "unconnected-(U7-A1-Pad2)") (class "Default")
      (node (ref "U7") (pin "2") (pinfunction "A1_2") (pintype "bidirectional"))
    )
    (net (code "136") (name "unconnected-(U7-A2-Pad3)") (class "Default")
      (node (ref "U7") (pin "3") (pinfunction "A2_3") (pintype "bidirectional"))
    )
    (net (code "137") (name "unconnected-(U7-A3-Pad4)") (class "Default")
      (node (ref "U7") (pin "4") (pinfunction "A3_4") (pintype "bidirectional"))
    )
    (net (code "138") (name "unconnected-(U7-A4-Pad5)") (class "Default")
      (node (ref "U7") (pin "5") (pinfunction "A4_5") (pintype "bidirectional"))
    )
    (net (code "139") (name "unconnected-(U7-A5-Pad6)") (class "Default")
      (node (ref "U7") (pin "6") (pinfunction "A5_6") (pintype "bidirectional"))
    )
    (net (code "140") (name "unconnected-(U7-A8-Pad9)") (class "Default")
      (node (ref "U7") (pin "9") (pinfunction "A8_9") (pintype "bidirectional"))
    )
    (net (code "141") (name "unconnected-(U7-B8-Pad11)") (class "Default")
      (node (ref "U7") (pin "11") (pinfunction "B8_11") (pintype "bidirectional"))
    )
    (net (code "142") (name "unconnected-(U8-A3-Pad4)") (class "Default")
      (node (ref "U8") (pin "4") (pinfunction "A3_4") (pintype "bidirectional"))
    )
    (net (code "143") (name "unconnected-(U8-A4-Pad5)") (class "Default")
      (node (ref "U8") (pin "5") (pinfunction "A4_5") (pintype "bidirectional"))
    )
    (net (code "144") (name "unconnected-(U8-A5-Pad6)") (class "Default")
      (node (ref "U8") (pin "6") (pinfunction "A5_6") (pintype "bidirectional"))
    )
    (net (code "145") (name "unconnected-(U8-A6-Pad7)") (class "Default")
      (node (ref "U8") (pin "7") (pinfunction "A6_7") (pintype "bidirectional"))
    )
    (net (code "146") (name "unconnected-(U8-A7-Pad8)") (class "Default")
      (node (ref "U8") (pin "8") (pinfunction "A7_8") (pintype "bidirectional"))
    )
    (net (code "147") (name "unconnected-(U8-A8-Pad9)") (class "Default")
      (node (ref "U8") (pin "9") (pinfunction "A8_9") (pintype "bidirectional"))
    )
    (net (code "148") (name "unconnected-(U8-B3-Pad16)") (class "Default")
      (node (ref "U8") (pin "16") (pinfunction "B3_16") (pintype "bidirectional"))
    )
  )
)
